# FTDI.net
KiCad netlist of a schematic drawn in Altium Designer
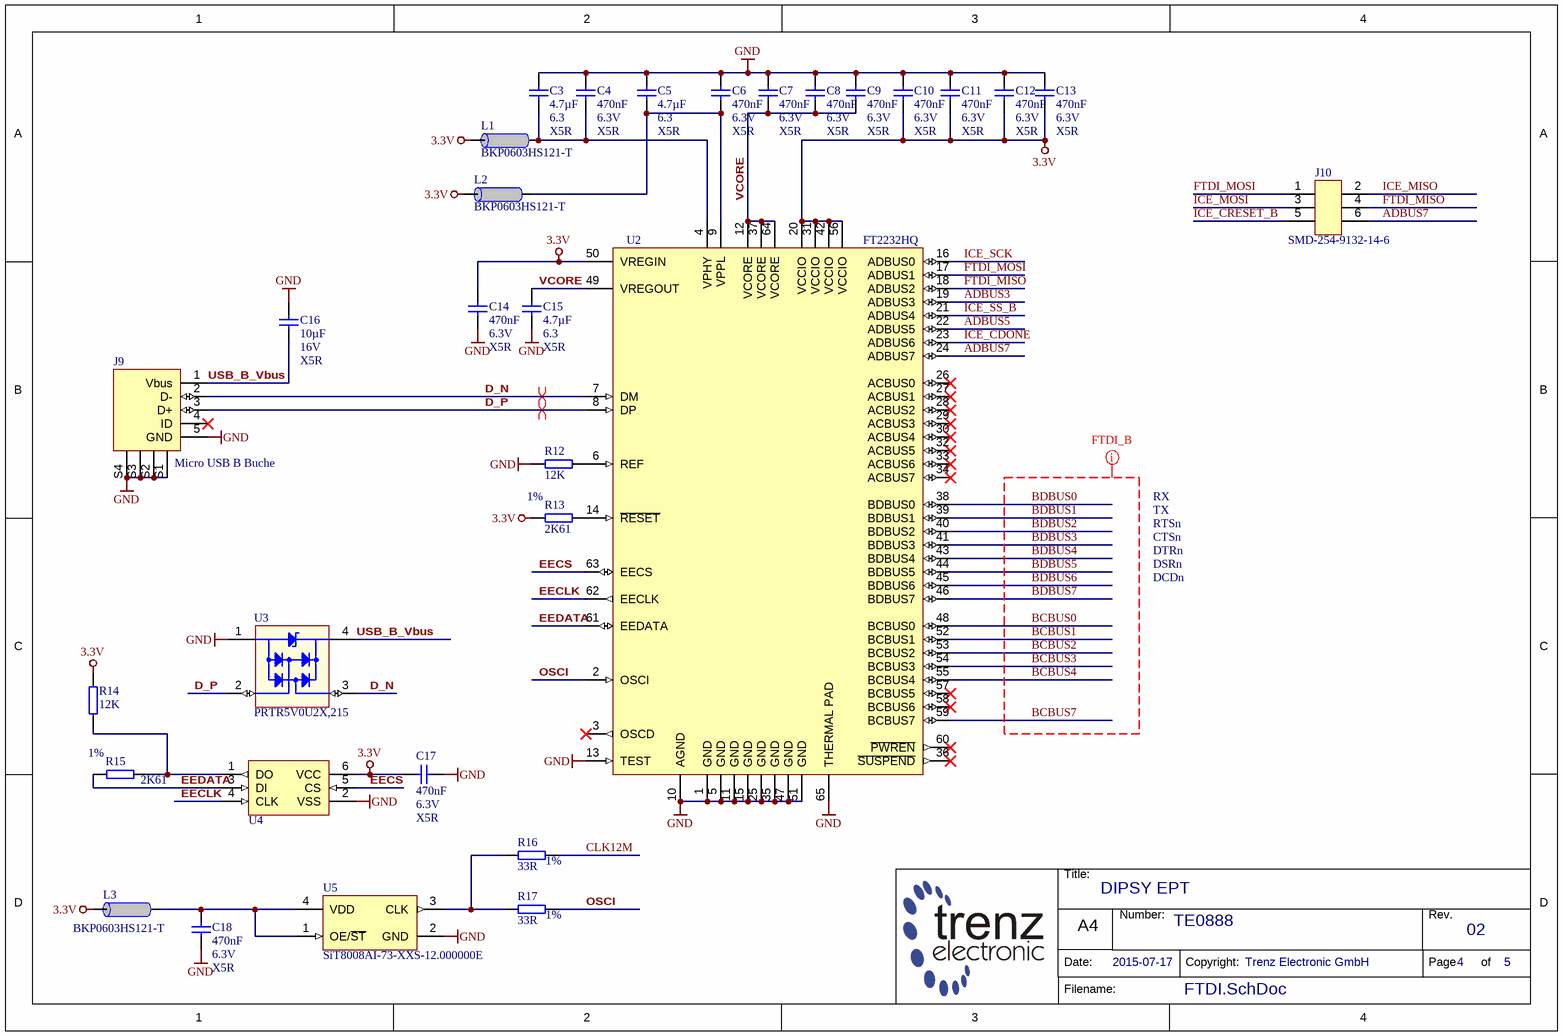
[diagram p0: FTDI.SchDoc]

(export (version "E")
  (design (tool "Eeschema 10.0.6"))
  (components
    (comp (ref "C3")
      (value "4.7µF")
      (footprint "CAPC1005X60N")
      (description "KON 4.7µF 6.3V X5R SMD 20%")
      (fields
        (field (name "VOLTAGE") "6.3")
        (field (name "TECHNOLOGY") "X5R")
        (field (name "TOLERANCE") "20%")
      )
      (libsource (lib "TE") (part "CAP-NP"))
    )
    (comp (ref "C4")
      (value "470nF")
      (footprint "CAPC0603X33N")
      (description "KON 470nF X5R 6.3V SMD 20%")
      (fields
        (field (name "VOLTAGE") "6.3V")
        (field (name "TECHNOLOGY") "X5R")
        (field (name "TOLERANCE") "20%")
      )
      (libsource (lib "TE") (part "CAP-NP"))
    )
    (comp (ref "C5")
      (value "4.7µF")
      (footprint "CAPC1005X60N")
      (description "KON 4.7µF 6.3V X5R SMD 20%")
      (fields
        (field (name "VOLTAGE") "6.3")
        (field (name "TECHNOLOGY") "X5R")
        (field (name "TOLERANCE") "20%")
      )
      (libsource (lib "TE") (part "CAP-NP"))
    )
    (comp (ref "C6")
      (value "470nF")
      (footprint "CAPC0603X33N")
      (description "KON 470nF X5R 6.3V SMD 20%")
      (fields
        (field (name "VOLTAGE") "6.3V")
        (field (name "TECHNOLOGY") "X5R")
        (field (name "TOLERANCE") "20%")
      )
      (libsource (lib "TE") (part "CAP-NP"))
    )
    (comp (ref "C7")
      (value "470nF")
      (footprint "CAPC0603X33N")
      (description "KON 470nF X5R 6.3V SMD 20%")
      (fields
        (field (name "VOLTAGE") "6.3V")
        (field (name "TECHNOLOGY") "X5R")
        (field (name "TOLERANCE") "20%")
      )
      (libsource (lib "TE") (part "CAP-NP"))
    )
    (comp (ref "C8")
      (value "470nF")
      (footprint "CAPC0603X33N")
      (description "KON 470nF X5R 6.3V SMD 20%")
      (fields
        (field (name "VOLTAGE") "6.3V")
        (field (name "TECHNOLOGY") "X5R")
        (field (name "TOLERANCE") "20%")
      )
      (libsource (lib "TE") (part "CAP-NP"))
    )
    (comp (ref "C9")
      (value "470nF")
      (footprint "CAPC0603X33N")
      (description "KON 470nF X5R 6.3V SMD 20%")
      (fields
        (field (name "VOLTAGE") "6.3V")
        (field (name "TECHNOLOGY") "X5R")
        (field (name "TOLERANCE") "20%")
      )
      (libsource (lib "TE") (part "CAP-NP"))
    )
    (comp (ref "C10")
      (value "470nF")
      (footprint "CAPC0603X33N")
      (description "KON 470nF X5R 6.3V SMD 20%")
      (fields
        (field (name "VOLTAGE") "6.3V")
        (field (name "TECHNOLOGY") "X5R")
        (field (name "TOLERANCE") "20%")
      )
      (libsource (lib "TE") (part "CAP-NP"))
    )
    (comp (ref "C11")
      (value "470nF")
      (footprint "CAPC0603X33N")
      (description "KON 470nF X5R 6.3V SMD 20%")
      (fields
        (field (name "VOLTAGE") "6.3V")
        (field (name "TECHNOLOGY") "X5R")
        (field (name "TOLERANCE") "20%")
      )
      (libsource (lib "TE") (part "CAP-NP"))
    )
    (comp (ref "C12")
      (value "470nF")
      (footprint "CAPC0603X33N")
      (description "KON 470nF X5R 6.3V SMD 20%")
      (fields
        (field (name "VOLTAGE") "6.3V")
        (field (name "TECHNOLOGY") "X5R")
        (field (name "TOLERANCE") "20%")
      )
      (libsource (lib "TE") (part "CAP-NP"))
    )
    (comp (ref "C13")
      (value "470nF")
      (footprint "CAPC0603X33N")
      (description "KON 470nF X5R 6.3V SMD 20%")
      (fields
        (field (name "VOLTAGE") "6.3V")
        (field (name "TECHNOLOGY") "X5R")
        (field (name "TOLERANCE") "20%")
      )
      (libsource (lib "TE") (part "CAP-NP"))
    )
    (comp (ref "C14")
      (value "470nF")
      (footprint "CAPC0603X33N")
      (description "KON 470nF X5R 6.3V SMD 20%")
      (fields
        (field (name "VOLTAGE") "6.3V")
        (field (name "TECHNOLOGY") "X5R")
        (field (name "TOLERANCE") "20%")
      )
      (libsource (lib "TE") (part "CAP-NP"))
    )
    (comp (ref "C15")
      (value "4.7µF")
      (footprint "CAPC1005X60N")
      (description "KON 4.7µF 6.3V X5R SMD 20%")
      (fields
        (field (name "VOLTAGE") "6.3")
        (field (name "TECHNOLOGY") "X5R")
        (field (name "TOLERANCE") "20%")
      )
      (libsource (lib "TE") (part "CAP-NP"))
    )
    (comp (ref "C16")
      (value "10µF")
      (footprint "CAPC1608X90N")
      (description "KON 10µF 16V X5R SMD 20%")
      (fields
        (field (name "VOLTAGE") "16V")
        (field (name "TECHNOLOGY") "X5R")
        (field (name "TOLERANCE") "20%")
      )
      (libsource (lib "TE") (part "CAP-NP"))
    )
    (comp (ref "C17")
      (value "470nF")
      (footprint "CAPC0603X33N")
      (description "KON 470nF X5R 6.3V SMD 20%")
      (fields
        (field (name "VOLTAGE") "6.3V")
        (field (name "TECHNOLOGY") "X5R")
        (field (name "TOLERANCE") "20%")
      )
      (libsource (lib "TE") (part "CAP-NP"))
    )
    (comp (ref "C18")
      (value "470nF")
      (footprint "CAPC0603X33N")
      (description "KON 470nF X5R 6.3V SMD 20%")
      (fields
        (field (name "VOLTAGE") "6.3V")
        (field (name "TECHNOLOGY") "X5R")
        (field (name "TOLERANCE") "20%")
      )
      (libsource (lib "TE") (part "CAP-NP"))
    )
    (comp (ref "J9")
      (value "Micro USB B Buche")
      (footprint "Micro USB B SMD W+P")
      (description "STE USB MICRO B Buchse SMD")
      (libsource (lib "TE") (part "M USB"))
    )
    (comp (ref "J10")
      (value "SMD-254-9132-14-6")
      (footprint "SMD-254-9132-14-6")
      (description "Stiftleiste gerade 2-reihig, 6pol. SMD")
      (libsource (lib "TE") (part "CON-6"))
    )
    (comp (ref "L1")
      (value "BKP0603HS121-T")
      (footprint "INDC0603X33N")
      (description "Ferritdurchführung SMD 0201")
      (fields (field (name "TOLERANCE") "25%"))
      (libsource (lib "TE") (part "Ferritperle"))
    )
    (comp (ref "L2")
      (value "BKP0603HS121-T")
      (footprint "INDC0603X33N")
      (description "Ferritdurchführung SMD 0201")
      (fields (field (name "TOLERANCE") "25%"))
      (libsource (lib "TE") (part "Ferritperle"))
    )
    (comp (ref "L3")
      (value "BKP0603HS121-T")
      (footprint "INDC0603X33N")
      (description "Ferritdurchführung SMD 0201")
      (fields (field (name "TOLERANCE") "25%"))
      (libsource (lib "TE") (part "Ferritperle"))
    )
    (comp (ref "R12")
      (value "12K")
      (footprint "RESC1005X40N")
      (description "WID SMD 12K 1% 0,063W")
      (libsource (lib "TE") (part "RES"))
    )
    (comp (ref "R13")
      (value "2K61")
      (footprint "RESC1005X40N")
      (description "WID SMD 2K61 1% 0,063W")
      (fields (field (name "TOLERANCE") "1%"))
      (libsource (lib "TE") (part "RES"))
    )
    (comp (ref "R14")
      (value "12K")
      (footprint "RESC1005X40N")
      (description "WID SMD 12K 1% 0,063W")
      (libsource (lib "TE") (part "RES"))
    )
    (comp (ref "R15")
      (value "2K61")
      (footprint "RESC1005X40N")
      (description "WID SMD 2K61 1% 0,063W")
      (fields (field (name "TOLERANCE") "1%"))
      (libsource (lib "TE") (part "RES"))
    )
    (comp (ref "R16")
      (value "33R")
      (footprint "RESC0603X26N")
      (description "WID SMD 33R 1% 0,05W")
      (fields (field (name "TOLERANCE") "1%"))
      (libsource (lib "TE") (part "RES"))
    )
    (comp (ref "R17")
      (value "33R")
      (footprint "RESC0603X26N")
      (description "WID SMD 33R 1% 0,05W")
      (fields (field (name "TOLERANCE") "1%"))
      (libsource (lib "TE") (part "RES"))
    )
    (comp (ref "U2")
      (value "FT2232HQ")
      (footprint "QFN50P900X900X100-65N-445")
      (libsource (lib "TE") (part "FT2232H"))
    )
    (comp (ref "U3")
      (value "PRTR5V0U2X,215")
      (footprint "SOT190P229X114-4N")
      (libsource (lib "TE") (part "CD143A-SRxx"))
    )
    (comp (ref "U4")
      (value "93AA56BT-I/OT")
      (footprint "SOT95P280X145-6N")
      (libsource (lib "TE") (part "93AA56x-OT"))
    )
    (comp (ref "U5")
      (value "SiT8008AI-73-XXS-12.000000E")
      (footprint "2016")
      (description "SiT8008AI-73-XXS-12.000000E MEMS Oszillator 12MHz")
      (libsource (lib "TE") (part "SiT8103"))
    )
  )
  (nets
    (net (code "1") (name "/ADBUS3") (class "Default")
      (node (ref "U2") (pin "19") (pinfunction "ADBUS3_19") (pintype "bidirectional"))
    )
    (net (code "2") (name "/ADBUS5") (class "Default")
      (node (ref "U2") (pin "22") (pinfunction "ADBUS5_22") (pintype "bidirectional"))
    )
    (net (code "3") (name "/ADBUS7") (class "Default")
      (node (ref "J10") (pin "6") (pintype "passive"))
      (node (ref "U2") (pin "24") (pinfunction "ADBUS7_24") (pintype "bidirectional"))
    )
    (net (code "4") (name "/BCBUS0") (class "Default")
      (node (ref "U2") (pin "48") (pinfunction "BCBUS0_48") (pintype "bidirectional"))
    )
    (net (code "5") (name "/BCBUS1") (class "Default")
      (node (ref "U2") (pin "52") (pinfunction "BCBUS1_52") (pintype "bidirectional"))
    )
    (net (code "6") (name "/BCBUS2") (class "Default")
      (node (ref "U2") (pin "53") (pinfunction "BCBUS2_53") (pintype "bidirectional"))
    )
    (net (code "7") (name "/BCBUS3") (class "Default")
      (node (ref "U2") (pin "54") (pinfunction "BCBUS3_54") (pintype "bidirectional"))
    )
    (net (code "8") (name "/BCBUS4") (class "Default")
      (node (ref "U2") (pin "55") (pinfunction "BCBUS4_55") (pintype "bidirectional"))
    )
    (net (code "9") (name "/BCBUS7") (class "Default")
      (node (ref "U2") (pin "59") (pinfunction "BCBUS7_59") (pintype "bidirectional"))
    )
    (net (code "10") (name "/BDBUS0") (class "Default")
      (node (ref "U2") (pin "38") (pinfunction "BDBUS0_38") (pintype "bidirectional"))
    )
    (net (code "11") (name "/BDBUS1") (class "Default")
      (node (ref "U2") (pin "39") (pinfunction "BDBUS1_39") (pintype "bidirectional"))
    )
    (net (code "12") (name "/BDBUS2") (class "Default")
      (node (ref "U2") (pin "40") (pinfunction "BDBUS2_40") (pintype "bidirectional"))
    )
    (net (code "13") (name "/BDBUS3") (class "Default")
      (node (ref "U2") (pin "41") (pinfunction "BDBUS3_41") (pintype "bidirectional"))
    )
    (net (code "14") (name "/BDBUS4") (class "Default")
      (node (ref "U2") (pin "43") (pinfunction "BDBUS4_43") (pintype "bidirectional"))
    )
    (net (code "15") (name "/BDBUS5") (class "Default")
      (node (ref "U2") (pin "44") (pinfunction "BDBUS5_44") (pintype "bidirectional"))
    )
    (net (code "16") (name "/BDBUS6") (class "Default")
      (node (ref "U2") (pin "45") (pinfunction "BDBUS6_45") (pintype "bidirectional"))
    )
    (net (code "17") (name "/BDBUS7") (class "Default")
      (node (ref "U2") (pin "46") (pinfunction "BDBUS7_46") (pintype "bidirectional"))
    )
    (net (code "18") (name "/CLK12M") (class "Default")
      (node (ref "R16") (pin "2") (pinfunction "2_2") (pintype "passive"))
    )
    (net (code "19") (name "/D_N") (class "Default")
      (node (ref "J9") (pin "2") (pinfunction "D-_2") (pintype "bidirectional"))
      (node (ref "U2") (pin "7") (pinfunction "DM_7") (pintype "input"))
      (node (ref "U3") (pin "3") (pinfunction "I/O_3") (pintype "bidirectional"))
    )
    (net (code "20") (name "/D_P") (class "Default")
      (node (ref "J9") (pin "3") (pinfunction "D+_3") (pintype "bidirectional"))
      (node (ref "U2") (pin "8") (pinfunction "DP_8") (pintype "input"))
      (node (ref "U3") (pin "2") (pinfunction "I/O_2") (pintype "bidirectional"))
    )
    (net (code "21") (name "/EECLK") (class "Default")
      (node (ref "U2") (pin "62") (pinfunction "EECLK_62") (pintype "output"))
      (node (ref "U4") (pin "4") (pinfunction "CLK_4") (pintype "input"))
    )
    (net (code "22") (name "/EECS") (class "Default")
      (node (ref "U2") (pin "63") (pinfunction "EECS_63") (pintype "bidirectional"))
      (node (ref "U4") (pin "5") (pinfunction "CS_5") (pintype "input"))
    )
    (net (code "23") (name "/EEDATA") (class "Default")
      (node (ref "R15") (pin "1") (pinfunction "1_1") (pintype "passive"))
      (node (ref "U2") (pin "61") (pinfunction "EEDATA_61") (pintype "bidirectional"))
      (node (ref "U4") (pin "3") (pinfunction "DI_3") (pintype "input"))
    )
    (net (code "24") (name "/FTDI_MISO") (class "Default")
      (node (ref "J10") (pin "4") (pintype "passive"))
      (node (ref "U2") (pin "18") (pinfunction "ADBUS2_18") (pintype "bidirectional"))
    )
    (net (code "25") (name "/FTDI_MOSI") (class "Default")
      (node (ref "J10") (pin "1") (pintype "passive"))
      (node (ref "U2") (pin "17") (pinfunction "ADBUS1_17") (pintype "bidirectional"))
    )
    (net (code "26") (name "/ICE_CDONE") (class "Default")
      (node (ref "U2") (pin "23") (pinfunction "ADBUS6_23") (pintype "bidirectional"))
    )
    (net (code "27") (name "/ICE_CRESET_B") (class "Default")
      (node (ref "J10") (pin "5") (pintype "passive"))
    )
    (net (code "28") (name "/ICE_MISO") (class "Default") (node (ref "J10") (pin "2") (pintype "passive")))
    (net (code "29") (name "/ICE_MOSI") (class "Default") (node (ref "J10") (pin "3") (pintype "passive")))
    (net (code "30") (name "/ICE_SCK") (class "Default")
      (node (ref "U2") (pin "16") (pinfunction "ADBUS0_16") (pintype "bidirectional"))
    )
    (net (code "31") (name "/ICE_SS_B") (class "Default")
      (node (ref "U2") (pin "21") (pinfunction "ADBUS4_21") (pintype "bidirectional"))
    )
    (net (code "32") (name "/OSCI") (class "Default")
      (node (ref "R17") (pin "2") (pinfunction "2_2") (pintype "passive"))
      (node (ref "U2") (pin "2") (pinfunction "OSCI_2") (pintype "input"))
    )
    (net (code "33") (name "/USB_B_Vbus") (class "Default")
      (node (ref "C16") (pin "2") (pinfunction "2_2") (pintype "passive"))
      (node (ref "J9") (pin "1") (pinfunction "Vbus_1") (pintype "power_in"))
      (node (ref "U3") (pin "4") (pinfunction "REF_4") (pintype "passive"))
    )
    (net (code "34") (name "/VCORE") (class "Default")
      (node (ref "C15") (pin "2") (pinfunction "2_2") (pintype "passive"))
      (node (ref "C7") (pin "1") (pinfunction "1_1") (pintype "passive"))
      (node (ref "C8") (pin "1") (pinfunction "1_1") (pintype "passive"))
      (node (ref "C9") (pin "1") (pinfunction "1_1") (pintype "passive"))
      (node (ref "U2") (pin "12") (pinfunction "VCORE_12") (pintype "power_in"))
      (node (ref "U2") (pin "37") (pinfunction "VCORE_37") (pintype "power_in"))
      (node (ref "U2") (pin "49") (pinfunction "VREGOUT_49") (pintype "power_in"))
      (node (ref "U2") (pin "64") (pinfunction "VCORE_64") (pintype "power_in"))
    )
    (net (code "35") (name "3.3V") (class "Default")
      (node (ref "C10") (pin "1") (pinfunction "1_1") (pintype "passive"))
      (node (ref "C11") (pin "1") (pinfunction "1_1") (pintype "passive"))
      (node (ref "C12") (pin "1") (pinfunction "1_1") (pintype "passive"))
      (node (ref "C13") (pin "1") (pinfunction "1_1") (pintype "passive"))
      (node (ref "C14") (pin "2") (pinfunction "2_2") (pintype "passive"))
      (node (ref "C17") (pin "1") (pinfunction "1_1") (pintype "passive"))
      (node (ref "L1") (pin "2") (pinfunction "2_2") (pintype "passive"))
      (node (ref "L2") (pin "2") (pinfunction "2_2") (pintype "passive"))
      (node (ref "L3") (pin "2") (pinfunction "2_2") (pintype "passive"))
      (node (ref "R13") (pin "1") (pinfunction "1_1") (pintype "passive"))
      (node (ref "R14") (pin "2") (pinfunction "2_2") (pintype "passive"))
      (node (ref "U2") (pin "20") (pinfunction "VCCIO_20") (pintype "power_in"))
      (node (ref "U2") (pin "31") (pinfunction "VCCIO_31") (pintype "power_in"))
      (node (ref "U2") (pin "42") (pinfunction "VCCIO_42") (pintype "power_in"))
      (node (ref "U2") (pin "50") (pinfunction "VREGIN_50") (pintype "power_in"))
      (node (ref "U2") (pin "56") (pinfunction "VCCIO_56") (pintype "power_in"))
      (node (ref "U4") (pin "6") (pinfunction "VCC_6") (pintype "power_in"))
    )
    (net (code "36") (name "GND") (class "Default")
      (node (ref "C10") (pin "2") (pinfunction "2_2") (pintype "passive"))
      (node (ref "C11") (pin "2") (pinfunction "2_2") (pintype "passive"))
      (node (ref "C12") (pin "2") (pinfunction "2_2") (pintype "passive"))
      (node (ref "C13") (pin "2") (pinfunction "2_2") (pintype "passive"))
      (node (ref "C14") (pin "1") (pinfunction "1_1") (pintype "passive"))
      (node (ref "C15") (pin "1") (pinfunction "1_1") (pintype "passive"))
      (node (ref "C16") (pin "1") (pinfunction "1_1") (pintype "passive"))
      (node (ref "C17") (pin "2") (pinfunction "2_2") (pintype "passive"))
      (node (ref "C18") (pin "1") (pinfunction "1_1") (pintype "passive"))
      (node (ref "C3") (pin "2") (pinfunction "2_2") (pintype "passive"))
      (node (ref "C4") (pin "2") (pinfunction "2_2") (pintype "passive"))
      (node (ref "C5") (pin "2") (pinfunction "2_2") (pintype "passive"))
      (node (ref "C6") (pin "2") (pinfunction "2_2") (pintype "passive"))
      (node (ref "C7") (pin "2") (pinfunction "2_2") (pintype "passive"))
      (node (ref "C8") (pin "2") (pinfunction "2_2") (pintype "passive"))
      (node (ref "C9") (pin "2") (pinfunction "2_2") (pintype "passive"))
      (node (ref "J9") (pin "5") (pinfunction "GND_5") (pintype "power_in"))
      (node (ref "J9") (pin "S1") (pinfunction "S1_S1") (pintype "passive"))
      (node (ref "J9") (pin "S2") (pinfunction "S2_S2") (pintype "passive"))
      (node (ref "J9") (pin "S3") (pinfunction "S3_S3") (pintype "passive"))
      (node (ref "J9") (pin "S4") (pinfunction "S4_S4") (pintype "passive"))
      (node (ref "R12") (pin "1") (pinfunction "1_1") (pintype "passive"))
      (node (ref "U2") (pin "1") (pinfunction "GND_1") (pintype "power_in"))
      (node (ref "U2") (pin "10") (pinfunction "AGND_10") (pintype "power_in"))
      (node (ref "U2") (pin "11") (pinfunction "GND_11") (pintype "power_in"))
      (node (ref "U2") (pin "13") (pinfunction "TEST_13") (pintype "input"))
      (node (ref "U2") (pin "15") (pinfunction "GND_15") (pintype "power_in"))
      (node (ref "U2") (pin "25") (pinfunction "GND_25") (pintype "power_in"))
      (node (ref "U2") (pin "35") (pinfunction "GND_35") (pintype "power_in"))
      (node (ref "U2") (pin "47") (pinfunction "GND_47") (pintype "power_in"))
      (node (ref "U2") (pin "5") (pinfunction "GND_5") (pintype "power_in"))
      (node (ref "U2") (pin "51") (pinfunction "GND_51") (pintype "power_in"))
      (node (ref "U2") (pin "65") (pinfunction "THERMAL_PAD_65") (pintype "passive"))
      (node (ref "U3") (pin "1") (pinfunction "GND_1") (pintype "passive"))
      (node (ref "U4") (pin "2") (pinfunction "VSS_2") (pintype "power_in"))
      (node (ref "U5") (pin "2") (pinfunction "GND_2") (pintype "power_in"))
    )
    (net (code "37") (name "Net-(U2-REF)") (class "Default")
      (node (ref "R12") (pin "2") (pinfunction "2_2") (pintype "passive"))
      (node (ref "U2") (pin "6") (pinfunction "REF_6") (pintype "input"))
    )
    (net (code "38") (name "Net-(U2-VPHY)") (class "Default")
      (node (ref "C3") (pin "1") (pinfunction "1_1") (pintype "passive"))
      (node (ref "C4") (pin "1") (pinfunction "1_1") (pintype "passive"))
      (node (ref "L1") (pin "1") (pinfunction "1_1") (pintype "passive"))
      (node (ref "U2") (pin "4") (pinfunction "VPHY_4") (pintype "power_in"))
    )
    (net (code "39") (name "Net-(U2-VPPL)") (class "Default")
      (node (ref "C5") (pin "1") (pinfunction "1_1") (pintype "passive"))
      (node (ref "C6") (pin "1") (pinfunction "1_1") (pintype "passive"))
      (node (ref "L2") (pin "1") (pinfunction "1_1") (pintype "passive"))
      (node (ref "U2") (pin "9") (pinfunction "VPPL_9") (pintype "power_in"))
    )
    (net (code "40") (name "Net-(U2-~{RESET})") (class "Default")
      (node (ref "R13") (pin "2") (pinfunction "2_2") (pintype "passive"))
      (node (ref "U2") (pin "14") (pinfunction "~{RESET}_14") (pintype "input"))
    )
    (net (code "41") (name "Net-(U4-DO)") (class "Default")
      (node (ref "R14") (pin "1") (pinfunction "1_1") (pintype "passive"))
      (node (ref "R15") (pin "2") (pinfunction "2_2") (pintype "passive"))
      (node (ref "U4") (pin "1") (pinfunction "DO_1") (pintype "output"))
    )
    (net (code "42") (name "Net-(U5-CLK)") (class "Default")
      (node (ref "R16") (pin "1") (pinfunction "1_1") (pintype "passive"))
      (node (ref "R17") (pin "1") (pinfunction "1_1") (pintype "passive"))
      (node (ref "U5") (pin "3") (pinfunction "CLK_3") (pintype "output"))
    )
    (net (code "43") (name "Net-(U5-OE{slash}~{ST})") (class "Default")
      (node (ref "C18") (pin "2") (pinfunction "2_2") (pintype "passive"))
      (node (ref "L3") (pin "1") (pinfunction "1_1") (pintype "passive"))
      (node (ref "U5") (pin "1") (pinfunction "OE/~{ST}_1") (pintype "input"))
      (node (ref "U5") (pin "4") (pinfunction "VDD_4") (pintype "power_in"))
    )
    (net (code "44") (name "unconnected-(J9-ID-Pad4)") (class "Default")
      (node (ref "J9") (pin "4") (pinfunction "ID_4") (pintype "passive+no_connect"))
    )
    (net (code "45") (name "unconnected-(U2-ACBUS0-Pad26)") (class "Default")
      (node (ref "U2") (pin "26") (pinfunction "ACBUS0_26") (pintype "bidirectional+no_connect"))
    )
    (net (code "46") (name "unconnected-(U2-ACBUS1-Pad27)") (class "Default")
      (node (ref "U2") (pin "27") (pinfunction "ACBUS1_27") (pintype "bidirectional+no_connect"))
    )
    (net (code "47") (name "unconnected-(U2-ACBUS2-Pad28)") (class "Default")
      (node (ref "U2") (pin "28") (pinfunction "ACBUS2_28") (pintype "bidirectional+no_connect"))
    )
    (net (code "48") (name "unconnected-(U2-ACBUS3-Pad29)") (class "Default")
      (node (ref "U2") (pin "29") (pinfunction "ACBUS3_29") (pintype "bidirectional+no_connect"))
    )
    (net (code "49") (name "unconnected-(U2-ACBUS4-Pad30)") (class "Default")
      (node (ref "U2") (pin "30") (pinfunction "ACBUS4_30") (pintype "bidirectional+no_connect"))
    )
    (net (code "50") (name "unconnected-(U2-ACBUS5-Pad32)") (class "Default")
      (node (ref "U2") (pin "32") (pinfunction "ACBUS5_32") (pintype "bidirectional+no_connect"))
    )
    (net (code "51") (name "unconnected-(U2-ACBUS6-Pad33)") (class "Default")
      (node (ref "U2") (pin "33") (pinfunction "ACBUS6_33") (pintype "bidirectional+no_connect"))
    )
    (net (code "52") (name "unconnected-(U2-ACBUS7-Pad34)") (class "Default")
      (node (ref "U2") (pin "34") (pinfunction "ACBUS7_34") (pintype "bidirectional+no_connect"))
    )
    (net (code "53") (name "unconnected-(U2-BCBUS5-Pad57)") (class "Default")
      (node (ref "U2") (pin "57") (pinfunction "BCBUS5_57") (pintype "bidirectional+no_connect"))
    )
    (net (code "54") (name "unconnected-(U2-BCBUS6-Pad58)") (class "Default")
      (node (ref "U2") (pin "58") (pinfunction "BCBUS6_58") (pintype "bidirectional+no_connect"))
    )
    (net (code "55") (name "unconnected-(U2-OSCD-Pad3)") (class "Default")
      (node (ref "U2") (pin "3") (pinfunction "OSCD_3") (pintype "output+no_connect"))
    )
    (net (code "56") (name "unconnected-(U2-~{PWREN}-Pad60)") (class "Default")
      (node (ref "U2") (pin "60") (pinfunction "~{PWREN}_60") (pintype "output+no_connect"))
    )
    (net (code "57") (name "unconnected-(U2-~{SUSPEND}-Pad36)") (class "Default")
      (node (ref "U2") (pin "36") (pinfunction "~{SUSPEND}_36") (pintype "output+no_connect"))
    )
  )
)
